# Digital_IO.net
KiCad netlist of a schematic drawn in Altium Designer
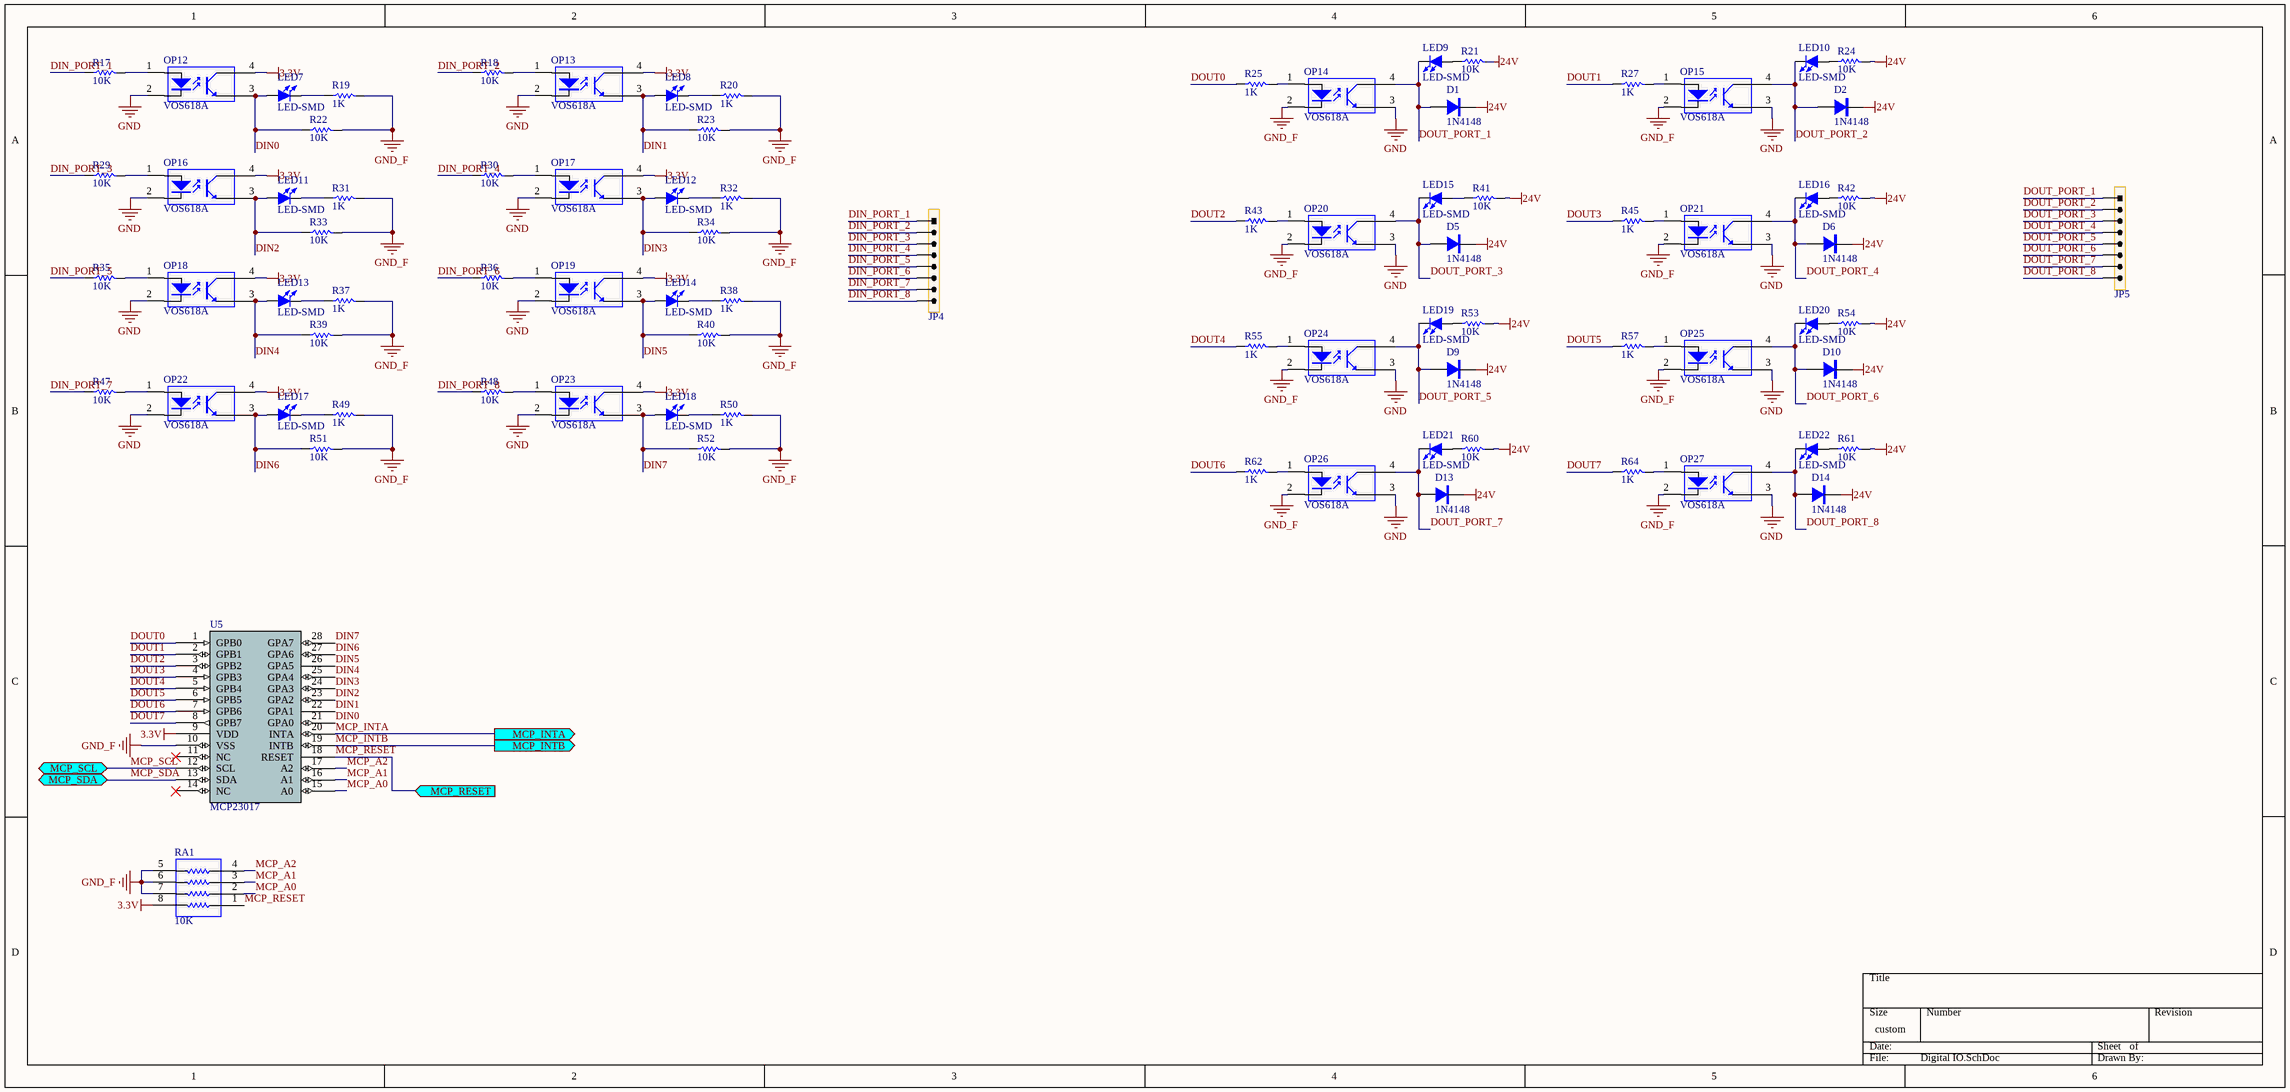
[diagram p0: Digital IO.SchDoc]

(export (version "E")
  (design (tool "Eeschema 10.0.6"))
  (components
    (comp (ref "D1")
      (value "1N4148")
      (footprint "SOD-323")
      (description "High speed switching diode")
      (fields (field (name "版权归属") "源创客"))
      (libsource (lib "Diode-Zener-Rectifier Bridge") (part "1N4148"))
    )
    (comp (ref "D2")
      (value "1N4148")
      (footprint "SOD-323")
      (description "High speed switching diode")
      (fields (field (name "版权归属") "源创客"))
      (libsource (lib "Diode-Zener-Rectifier Bridge") (part "1N4148"))
    )
    (comp (ref "D5")
      (value "1N4148")
      (footprint "SOD-323")
      (description "High speed switching diode")
      (fields (field (name "版权归属") "源创客"))
      (libsource (lib "Diode-Zener-Rectifier Bridge") (part "1N4148"))
    )
    (comp (ref "D6")
      (value "1N4148")
      (footprint "SOD-323")
      (description "High speed switching diode")
      (fields (field (name "版权归属") "源创客"))
      (libsource (lib "Diode-Zener-Rectifier Bridge") (part "1N4148"))
    )
    (comp (ref "D9")
      (value "1N4148")
      (footprint "SOD-323")
      (description "High speed switching diode")
      (fields (field (name "版权归属") "源创客"))
      (libsource (lib "Diode-Zener-Rectifier Bridge") (part "1N4148"))
    )
    (comp (ref "D10")
      (value "1N4148")
      (footprint "SOD-323")
      (description "High speed switching diode")
      (fields (field (name "版权归属") "源创客"))
      (libsource (lib "Diode-Zener-Rectifier Bridge") (part "1N4148"))
    )
    (comp (ref "D13")
      (value "1N4148")
      (footprint "SOD-323")
      (description "High speed switching diode")
      (fields (field (name "版权归属") "源创客"))
      (libsource (lib "Diode-Zener-Rectifier Bridge") (part "1N4148"))
    )
    (comp (ref "D14")
      (value "1N4148")
      (footprint "SOD-323")
      (description "High speed switching diode")
      (fields (field (name "版权归属") "源创客"))
      (libsource (lib "Diode-Zener-Rectifier Bridge") (part "1N4148"))
    )
    (comp (ref "JP4")
      (value "HDR-1X8")
      (footprint "KF-8P-BLK-H-3.81")
      (description "8P Connector")
      (fields (field (name "版权归属") "源创客"))
      (libsource (lib "Connectors") (part "Header 8"))
    )
    (comp (ref "JP5")
      (value "HDR-1X8")
      (footprint "KF-8P-BLK-H-3.81")
      (description "8P Connector")
      (fields (field (name "版权归属") "源创客"))
      (libsource (lib "Connectors") (part "Header 8"))
    )
    (comp (ref "LED7")
      (value "LED-SMD")
      (footprint "LED 0603G")
      (description "Patch LED")
      (fields (field (name "版权归属") "源创客"))
      (libsource (lib "LED") (part "LED-SMD"))
    )
    (comp (ref "LED8")
      (value "LED-SMD")
      (footprint "LED 0603G")
      (description "Patch LED")
      (fields (field (name "版权归属") "源创客"))
      (libsource (lib "LED") (part "LED-SMD"))
    )
    (comp (ref "LED9")
      (value "LED-SMD")
      (footprint "LED 0603B")
      (description "Patch LED")
      (fields (field (name "版权归属") "源创客"))
      (libsource (lib "LED") (part "LED-SMD"))
    )
    (comp (ref "LED10")
      (value "LED-SMD")
      (footprint "LED 0603B")
      (description "Patch LED")
      (fields (field (name "版权归属") "源创客"))
      (libsource (lib "LED") (part "LED-SMD"))
    )
    (comp (ref "LED11")
      (value "LED-SMD")
      (footprint "LED 0603G")
      (description "Patch LED")
      (fields (field (name "版权归属") "源创客"))
      (libsource (lib "LED") (part "LED-SMD"))
    )
    (comp (ref "LED12")
      (value "LED-SMD")
      (footprint "LED 0603G")
      (description "Patch LED")
      (fields (field (name "版权归属") "源创客"))
      (libsource (lib "LED") (part "LED-SMD"))
    )
    (comp (ref "LED13")
      (value "LED-SMD")
      (footprint "LED 0603G")
      (description "Patch LED")
      (fields (field (name "版权归属") "源创客"))
      (libsource (lib "LED") (part "LED-SMD"))
    )
    (comp (ref "LED14")
      (value "LED-SMD")
      (footprint "LED 0603G")
      (description "Patch LED")
      (fields (field (name "版权归属") "源创客"))
      (libsource (lib "LED") (part "LED-SMD"))
    )
    (comp (ref "LED15")
      (value "LED-SMD")
      (footprint "LED 0603B")
      (description "Patch LED")
      (fields (field (name "版权归属") "源创客"))
      (libsource (lib "LED") (part "LED-SMD"))
    )
    (comp (ref "LED16")
      (value "LED-SMD")
      (footprint "LED 0603B")
      (description "Patch LED")
      (fields (field (name "版权归属") "源创客"))
      (libsource (lib "LED") (part "LED-SMD"))
    )
    (comp (ref "LED17")
      (value "LED-SMD")
      (footprint "LED 0603G")
      (description "Patch LED")
      (fields (field (name "版权归属") "源创客"))
      (libsource (lib "LED") (part "LED-SMD"))
    )
    (comp (ref "LED18")
      (value "LED-SMD")
      (footprint "LED 0603G")
      (description "Patch LED")
      (fields (field (name "版权归属") "源创客"))
      (libsource (lib "LED") (part "LED-SMD"))
    )
    (comp (ref "LED19")
      (value "LED-SMD")
      (footprint "LED 0603B")
      (description "Patch LED")
      (fields (field (name "版权归属") "源创客"))
      (libsource (lib "LED") (part "LED-SMD"))
    )
    (comp (ref "LED20")
      (value "LED-SMD")
      (footprint "LED 0603B")
      (description "Patch LED")
      (fields (field (name "版权归属") "源创客"))
      (libsource (lib "LED") (part "LED-SMD"))
    )
    (comp (ref "LED21")
      (value "LED-SMD")
      (footprint "LED 0603B")
      (description "Patch LED")
      (fields (field (name "版权归属") "源创客"))
      (libsource (lib "LED") (part "LED-SMD"))
    )
    (comp (ref "LED22")
      (value "LED-SMD")
      (footprint "LED 0603B")
      (description "Patch LED")
      (fields (field (name "版权归属") "源创客"))
      (libsource (lib "LED") (part "LED-SMD"))
    )
    (comp (ref "OP12")
      (value "VOS618A")
      (footprint "VOS618A-SSOP4")
      (libsource (lib "Sensing Element") (part "VOS618A"))
    )
    (comp (ref "OP13")
      (value "VOS618A")
      (footprint "VOS618A-SSOP4")
      (libsource (lib "Sensing Element") (part "VOS618A"))
    )
    (comp (ref "OP14")
      (value "VOS618A")
      (footprint "VOS618A-SSOP4")
      (libsource (lib "Sensing Element") (part "VOS618A"))
    )
    (comp (ref "OP15")
      (value "VOS618A")
      (footprint "VOS618A-SSOP4")
      (libsource (lib "Sensing Element") (part "VOS618A"))
    )
    (comp (ref "OP16")
      (value "VOS618A")
      (footprint "VOS618A-SSOP4")
      (libsource (lib "Sensing Element") (part "VOS618A"))
    )
    (comp (ref "OP17")
      (value "VOS618A")
      (footprint "VOS618A-SSOP4")
      (libsource (lib "Sensing Element") (part "VOS618A"))
    )
    (comp (ref "OP18")
      (value "VOS618A")
      (footprint "VOS618A-SSOP4")
      (libsource (lib "Sensing Element") (part "VOS618A"))
    )
    (comp (ref "OP19")
      (value "VOS618A")
      (footprint "VOS618A-SSOP4")
      (libsource (lib "Sensing Element") (part "VOS618A"))
    )
    (comp (ref "OP20")
      (value "VOS618A")
      (footprint "VOS618A-SSOP4")
      (libsource (lib "Sensing Element") (part "VOS618A"))
    )
    (comp (ref "OP21")
      (value "VOS618A")
      (footprint "VOS618A-SSOP4")
      (libsource (lib "Sensing Element") (part "VOS618A"))
    )
    (comp (ref "OP22")
      (value "VOS618A")
      (footprint "VOS618A-SSOP4")
      (libsource (lib "Sensing Element") (part "VOS618A"))
    )
    (comp (ref "OP23")
      (value "VOS618A")
      (footprint "VOS618A-SSOP4")
      (libsource (lib "Sensing Element") (part "VOS618A"))
    )
    (comp (ref "OP24")
      (value "VOS618A")
      (footprint "VOS618A-SSOP4")
      (libsource (lib "Sensing Element") (part "VOS618A"))
    )
    (comp (ref "OP25")
      (value "VOS618A")
      (footprint "VOS618A-SSOP4")
      (libsource (lib "Sensing Element") (part "VOS618A"))
    )
    (comp (ref "OP26")
      (value "VOS618A")
      (footprint "VOS618A-SSOP4")
      (libsource (lib "Sensing Element") (part "VOS618A"))
    )
    (comp (ref "OP27")
      (value "VOS618A")
      (footprint "VOS618A-SSOP4")
      (libsource (lib "Sensing Element") (part "VOS618A"))
    )
    (comp (ref "R17")
      (value "10K")
      (footprint "R 0603")
      (description "Chip resistor")
      (fields (field (name "版权归属") "源创客"))
      (libsource (lib "Passive (Resistor-Capacitor-Inductor-Veristor-Ferrite)") (part "R"))
    )
    (comp (ref "R18")
      (value "10K")
      (footprint "R 0603")
      (description "Chip resistor")
      (fields (field (name "版权归属") "源创客"))
      (libsource (lib "Passive (Resistor-Capacitor-Inductor-Veristor-Ferrite)") (part "R"))
    )
    (comp (ref "R19")
      (value "1K")
      (footprint "R 0603")
      (description "Chip resistor")
      (fields (field (name "版权归属") "源创客"))
      (libsource (lib "Passive (Resistor-Capacitor-Inductor-Veristor-Ferrite)") (part "R"))
    )
    (comp (ref "R20")
      (value "1K")
      (footprint "R 0603")
      (description "Chip resistor")
      (fields (field (name "版权归属") "源创客"))
      (libsource (lib "Passive (Resistor-Capacitor-Inductor-Veristor-Ferrite)") (part "R"))
    )
    (comp (ref "R21")
      (value "10K")
      (footprint "R 0603")
      (description "Chip resistor")
      (fields (field (name "版权归属") "源创客"))
      (libsource (lib "Passive (Resistor-Capacitor-Inductor-Veristor-Ferrite)") (part "R"))
    )
    (comp (ref "R22")
      (value "10K")
      (footprint "R 0603")
      (description "Chip resistor")
      (fields (field (name "版权归属") "源创客"))
      (libsource (lib "Passive (Resistor-Capacitor-Inductor-Veristor-Ferrite)") (part "R"))
    )
    (comp (ref "R23")
      (value "10K")
      (footprint "R 0603")
      (description "Chip resistor")
      (fields (field (name "版权归属") "源创客"))
      (libsource (lib "Passive (Resistor-Capacitor-Inductor-Veristor-Ferrite)") (part "R"))
    )
    (comp (ref "R24")
      (value "10K")
      (footprint "R 0603")
      (description "Chip resistor")
      (fields (field (name "版权归属") "源创客"))
      (libsource (lib "Passive (Resistor-Capacitor-Inductor-Veristor-Ferrite)") (part "R"))
    )
    (comp (ref "R25")
      (value "1K")
      (footprint "R 0603")
      (description "Chip resistor")
      (fields (field (name "版权归属") "源创客"))
      (libsource (lib "Passive (Resistor-Capacitor-Inductor-Veristor-Ferrite)") (part "R"))
    )
    (comp (ref "R27")
      (value "1K")
      (footprint "R 0603")
      (description "Chip resistor")
      (fields (field (name "版权归属") "源创客"))
      (libsource (lib "Passive (Resistor-Capacitor-Inductor-Veristor-Ferrite)") (part "R"))
    )
    (comp (ref "R29")
      (value "10K")
      (footprint "R 0603")
      (description "Chip resistor")
      (fields (field (name "版权归属") "源创客"))
      (libsource (lib "Passive (Resistor-Capacitor-Inductor-Veristor-Ferrite)") (part "R"))
    )
    (comp (ref "R30")
      (value "10K")
      (footprint "R 0603")
      (description "Chip resistor")
      (fields (field (name "版权归属") "源创客"))
      (libsource (lib "Passive (Resistor-Capacitor-Inductor-Veristor-Ferrite)") (part "R"))
    )
    (comp (ref "R31")
      (value "1K")
      (footprint "R 0603")
      (description "Chip resistor")
      (fields (field (name "版权归属") "源创客"))
      (libsource (lib "Passive (Resistor-Capacitor-Inductor-Veristor-Ferrite)") (part "R"))
    )
    (comp (ref "R32")
      (value "1K")
      (footprint "R 0603")
      (description "Chip resistor")
      (fields (field (name "版权归属") "源创客"))
      (libsource (lib "Passive (Resistor-Capacitor-Inductor-Veristor-Ferrite)") (part "R"))
    )
    (comp (ref "R33")
      (value "10K")
      (footprint "R 0603")
      (description "Chip resistor")
      (fields (field (name "版权归属") "源创客"))
      (libsource (lib "Passive (Resistor-Capacitor-Inductor-Veristor-Ferrite)") (part "R"))
    )
    (comp (ref "R34")
      (value "10K")
      (footprint "R 0603")
      (description "Chip resistor")
      (fields (field (name "版权归属") "源创客"))
      (libsource (lib "Passive (Resistor-Capacitor-Inductor-Veristor-Ferrite)") (part "R"))
    )
    (comp (ref "R35")
      (value "10K")
      (footprint "R 0603")
      (description "Chip resistor")
      (fields (field (name "版权归属") "源创客"))
      (libsource (lib "Passive (Resistor-Capacitor-Inductor-Veristor-Ferrite)") (part "R"))
    )
    (comp (ref "R36")
      (value "10K")
      (footprint "R 0603")
      (description "Chip resistor")
      (fields (field (name "版权归属") "源创客"))
      (libsource (lib "Passive (Resistor-Capacitor-Inductor-Veristor-Ferrite)") (part "R"))
    )
    (comp (ref "R37")
      (value "1K")
      (footprint "R 0603")
      (description "Chip resistor")
      (fields (field (name "版权归属") "源创客"))
      (libsource (lib "Passive (Resistor-Capacitor-Inductor-Veristor-Ferrite)") (part "R"))
    )
    (comp (ref "R38")
      (value "1K")
      (footprint "R 0603")
      (description "Chip resistor")
      (fields (field (name "版权归属") "源创客"))
      (libsource (lib "Passive (Resistor-Capacitor-Inductor-Veristor-Ferrite)") (part "R"))
    )
    (comp (ref "R39")
      (value "10K")
      (footprint "R 0603")
      (description "Chip resistor")
      (fields (field (name "版权归属") "源创客"))
      (libsource (lib "Passive (Resistor-Capacitor-Inductor-Veristor-Ferrite)") (part "R"))
    )
    (comp (ref "R40")
      (value "10K")
      (footprint "R 0603")
      (description "Chip resistor")
      (fields (field (name "版权归属") "源创客"))
      (libsource (lib "Passive (Resistor-Capacitor-Inductor-Veristor-Ferrite)") (part "R"))
    )
    (comp (ref "R41")
      (value "10K")
      (footprint "R 0603")
      (description "Chip resistor")
      (fields (field (name "版权归属") "源创客"))
      (libsource (lib "Passive (Resistor-Capacitor-Inductor-Veristor-Ferrite)") (part "R"))
    )
    (comp (ref "R42")
      (value "10K")
      (footprint "R 0603")
      (description "Chip resistor")
      (fields (field (name "版权归属") "源创客"))
      (libsource (lib "Passive (Resistor-Capacitor-Inductor-Veristor-Ferrite)") (part "R"))
    )
    (comp (ref "R43")
      (value "1K")
      (footprint "R 0603")
      (description "Chip resistor")
      (fields (field (name "版权归属") "源创客"))
      (libsource (lib "Passive (Resistor-Capacitor-Inductor-Veristor-Ferrite)") (part "R"))
    )
    (comp (ref "R45")
      (value "1K")
      (footprint "R 0603")
      (description "Chip resistor")
      (fields (field (name "版权归属") "源创客"))
      (libsource (lib "Passive (Resistor-Capacitor-Inductor-Veristor-Ferrite)") (part "R"))
    )
    (comp (ref "R47")
      (value "10K")
      (footprint "R 0603")
      (description "Chip resistor")
      (fields (field (name "版权归属") "源创客"))
      (libsource (lib "Passive (Resistor-Capacitor-Inductor-Veristor-Ferrite)") (part "R"))
    )
    (comp (ref "R48")
      (value "10K")
      (footprint "R 0603")
      (description "Chip resistor")
      (fields (field (name "版权归属") "源创客"))
      (libsource (lib "Passive (Resistor-Capacitor-Inductor-Veristor-Ferrite)") (part "R"))
    )
    (comp (ref "R49")
      (value "1K")
      (footprint "R 0603")
      (description "Chip resistor")
      (fields (field (name "版权归属") "源创客"))
      (libsource (lib "Passive (Resistor-Capacitor-Inductor-Veristor-Ferrite)") (part "R"))
    )
    (comp (ref "R50")
      (value "1K")
      (footprint "R 0603")
      (description "Chip resistor")
      (fields (field (name "版权归属") "源创客"))
      (libsource (lib "Passive (Resistor-Capacitor-Inductor-Veristor-Ferrite)") (part "R"))
    )
    (comp (ref "R51")
      (value "10K")
      (footprint "R 0603")
      (description "Chip resistor")
      (fields (field (name "版权归属") "源创客"))
      (libsource (lib "Passive (Resistor-Capacitor-Inductor-Veristor-Ferrite)") (part "R"))
    )
    (comp (ref "R52")
      (value "10K")
      (footprint "R 0603")
      (description "Chip resistor")
      (fields (field (name "版权归属") "源创客"))
      (libsource (lib "Passive (Resistor-Capacitor-Inductor-Veristor-Ferrite)") (part "R"))
    )
    (comp (ref "R53")
      (value "10K")
      (footprint "R 0603")
      (description "Chip resistor")
      (fields (field (name "版权归属") "源创客"))
      (libsource (lib "Passive (Resistor-Capacitor-Inductor-Veristor-Ferrite)") (part "R"))
    )
    (comp (ref "R54")
      (value "10K")
      (footprint "R 0603")
      (description "Chip resistor")
      (fields (field (name "版权归属") "源创客"))
      (libsource (lib "Passive (Resistor-Capacitor-Inductor-Veristor-Ferrite)") (part "R"))
    )
    (comp (ref "R55")
      (value "1K")
      (footprint "R 0603")
      (description "Chip resistor")
      (fields (field (name "版权归属") "源创客"))
      (libsource (lib "Passive (Resistor-Capacitor-Inductor-Veristor-Ferrite)") (part "R"))
    )
    (comp (ref "R57")
      (value "1K")
      (footprint "R 0603")
      (description "Chip resistor")
      (fields (field (name "版权归属") "源创客"))
      (libsource (lib "Passive (Resistor-Capacitor-Inductor-Veristor-Ferrite)") (part "R"))
    )
    (comp (ref "R60")
      (value "10K")
      (footprint "R 0603")
      (description "Chip resistor")
      (fields (field (name "版权归属") "源创客"))
      (libsource (lib "Passive (Resistor-Capacitor-Inductor-Veristor-Ferrite)") (part "R"))
    )
    (comp (ref "R61")
      (value "10K")
      (footprint "R 0603")
      (description "Chip resistor")
      (fields (field (name "版权归属") "源创客"))
      (libsource (lib "Passive (Resistor-Capacitor-Inductor-Veristor-Ferrite)") (part "R"))
    )
    (comp (ref "R62")
      (value "1K")
      (footprint "R 0603")
      (description "Chip resistor")
      (fields (field (name "版权归属") "源创客"))
      (libsource (lib "Passive (Resistor-Capacitor-Inductor-Veristor-Ferrite)") (part "R"))
    )
    (comp (ref "R64")
      (value "1K")
      (footprint "R 0603")
      (description "Chip resistor")
      (fields (field (name "版权归属") "源创客"))
      (libsource (lib "Passive (Resistor-Capacitor-Inductor-Veristor-Ferrite)") (part "R"))
    )
    (comp (ref "RA1")
      (value "10K")
      (footprint "RA1206 (4x0603)")
      (description "4 way Chip Resistor Array")
      (libsource (lib "Passive (Resistor-Capacitor-Inductor-Veristor-Ferrite)") (part "R-ARR"))
    )
    (comp (ref "U5")
      (value "MCP23017")
      (footprint "SOIC28")
      (libsource (lib "Integrated Circuit") (part "MCP23017"))
    )
  )
  (nets
    (net (code "1") (name "/DIN0") (class "Default")
      (node (ref "LED7") (pin "1") (pinfunction "A_1") (pintype "passive"))
      (node (ref "OP12") (pin "3") (pinfunction "E_3") (pintype "passive"))
      (node (ref "R22") (pin "1") (pinfunction "1_1") (pintype "passive"))
      (node (ref "U5") (pin "21") (pinfunction "GPA0_21") (pintype "bidirectional"))
    )
    (net (code "2") (name "/DIN1") (class "Default")
      (node (ref "LED8") (pin "1") (pinfunction "A_1") (pintype "passive"))
      (node (ref "OP13") (pin "3") (pinfunction "E_3") (pintype "passive"))
      (node (ref "R23") (pin "1") (pinfunction "1_1") (pintype "passive"))
      (node (ref "U5") (pin "22") (pinfunction "GPA1_22") (pintype "power_in"))
    )
    (net (code "3") (name "/DIN2") (class "Default")
      (node (ref "LED11") (pin "1") (pinfunction "A_1") (pintype "passive"))
      (node (ref "OP16") (pin "3") (pinfunction "E_3") (pintype "passive"))
      (node (ref "R33") (pin "1") (pinfunction "1_1") (pintype "passive"))
      (node (ref "U5") (pin "23") (pinfunction "GPA2_23") (pintype "bidirectional"))
    )
    (net (code "4") (name "/DIN3") (class "Default")
      (node (ref "LED12") (pin "1") (pinfunction "A_1") (pintype "passive"))
      (node (ref "OP17") (pin "3") (pinfunction "E_3") (pintype "passive"))
      (node (ref "R34") (pin "1") (pinfunction "1_1") (pintype "passive"))
      (node (ref "U5") (pin "24") (pinfunction "GPA3_24") (pintype "bidirectional"))
    )
    (net (code "5") (name "/DIN4") (class "Default")
      (node (ref "LED13") (pin "1") (pinfunction "A_1") (pintype "passive"))
      (node (ref "OP18") (pin "3") (pinfunction "E_3") (pintype "passive"))
      (node (ref "R39") (pin "1") (pinfunction "1_1") (pintype "passive"))
      (node (ref "U5") (pin "25") (pinfunction "GPA4_25") (pintype "bidirectional"))
    )
    (net (code "6") (name "/DIN5") (class "Default")
      (node (ref "LED14") (pin "1") (pinfunction "A_1") (pintype "passive"))
      (node (ref "OP19") (pin "3") (pinfunction "E_3") (pintype "passive"))
      (node (ref "R40") (pin "1") (pinfunction "1_1") (pintype "passive"))
      (node (ref "U5") (pin "26") (pinfunction "GPA5_26") (pintype "power_in"))
    )
    (net (code "7") (name "/DIN6") (class "Default")
      (node (ref "LED17") (pin "1") (pinfunction "A_1") (pintype "passive"))
      (node (ref "OP22") (pin "3") (pinfunction "E_3") (pintype "passive"))
      (node (ref "R51") (pin "1") (pinfunction "1_1") (pintype "passive"))
      (node (ref "U5") (pin "27") (pinfunction "GPA6_27") (pintype "bidirectional"))
    )
    (net (code "8") (name "/DIN7") (class "Default")
      (node (ref "LED18") (pin "1") (pinfunction "A_1") (pintype "passive"))
      (node (ref "OP23") (pin "3") (pinfunction "E_3") (pintype "passive"))
      (node (ref "R52") (pin "1") (pinfunction "1_1") (pintype "passive"))
      (node (ref "U5") (pin "28") (pinfunction "GPA7_28") (pintype "bidirectional"))
    )
    (net (code "9") (name "/DIN_PORT_1") (class "Default")
      (node (ref "JP4") (pin "1") (pintype "passive"))
      (node (ref "R17") (pin "1") (pinfunction "1_1") (pintype "passive"))
    )
    (net (code "10") (name "/DIN_PORT_2") (class "Default")
      (node (ref "JP4") (pin "2") (pintype "passive"))
      (node (ref "R18") (pin "1") (pinfunction "1_1") (pintype "passive"))
    )
    (net (code "11") (name "/DIN_PORT_3") (class "Default")
      (node (ref "JP4") (pin "3") (pintype "passive"))
      (node (ref "R29") (pin "1") (pinfunction "1_1") (pintype "passive"))
    )
    (net (code "12") (name "/DIN_PORT_4") (class "Default")
      (node (ref "JP4") (pin "4") (pintype "passive"))
      (node (ref "R30") (pin "1") (pinfunction "1_1") (pintype "passive"))
    )
    (net (code "13") (name "/DIN_PORT_5") (class "Default")
      (node (ref "JP4") (pin "5") (pintype "passive"))
      (node (ref "R35") (pin "1") (pinfunction "1_1") (pintype "passive"))
    )
    (net (code "14") (name "/DIN_PORT_6") (class "Default")
      (node (ref "JP4") (pin "6") (pintype "passive"))
      (node (ref "R36") (pin "1") (pinfunction "1_1") (pintype "passive"))
    )
    (net (code "15") (name "/DIN_PORT_7") (class "Default")
      (node (ref "JP4") (pin "7") (pintype "passive"))
      (node (ref "R47") (pin "1") (pinfunction "1_1") (pintype "passive"))
    )
    (net (code "16") (name "/DIN_PORT_8") (class "Default")
      (node (ref "JP4") (pin "8") (pintype "passive"))
      (node (ref "R48") (pin "1") (pinfunction "1_1") (pintype "passive"))
    )
    (net (code "17") (name "/DOUT0") (class "Default")
      (node (ref "R25") (pin "1") (pinfunction "1_1") (pintype "passive"))
      (node (ref "U5") (pin "1") (pinfunction "GPB0_1") (pintype "input"))
    )
    (net (code "18") (name "/DOUT1") (class "Default")
      (node (ref "R27") (pin "1") (pinfunction "1_1") (pintype "passive"))
      (node (ref "U5") (pin "2") (pinfunction "GPB1_2") (pintype "bidirectional"))
    )
    (net (code "19") (name "/DOUT2") (class "Default")
      (node (ref "R43") (pin "1") (pinfunction "1_1") (pintype "passive"))
      (node (ref "U5") (pin "3") (pinfunction "GPB2_3") (pintype "bidirectional"))
    )
    (net (code "20") (name "/DOUT3") (class "Default")
      (node (ref "R45") (pin "1") (pinfunction "1_1") (pintype "passive"))
      (node (ref "U5") (pin "4") (pinfunction "GPB3_4") (pintype "input"))
    )
    (net (code "21") (name "/DOUT4") (class "Default")
      (node (ref "R55") (pin "1") (pinfunction "1_1") (pintype "passive"))
      (node (ref "U5") (pin "5") (pinfunction "GPB4_5") (pintype "input"))
    )
    (net (code "22") (name "/DOUT5") (class "Default")
      (node (ref "R57") (pin "1") (pinfunction "1_1") (pintype "passive"))
      (node (ref "U5") (pin "6") (pinfunction "GPB5_6") (pintype "input"))
    )
    (net (code "23") (name "/DOUT6") (class "Default")
      (node (ref "R62") (pin "1") (pinfunction "1_1") (pintype "passive"))
      (node (ref "U5") (pin "7") (pinfunction "GPB6_7") (pintype "input"))
    )
    (net (code "24") (name "/DOUT7") (class "Default")
      (node (ref "R64") (pin "1") (pinfunction "1_1") (pintype "passive"))
      (node (ref "U5") (pin "8") (pinfunction "GPB7_8") (pintype "output"))
    )
    (net (code "25") (name "/DOUT_PORT_1") (class "Default")
      (node (ref "D1") (pin "1") (pinfunction "A_1") (pintype "passive"))
      (node (ref "JP5") (pin "1") (pintype "passive"))
      (node (ref "LED9") (pin "2") (pinfunction "K_2") (pintype "passive"))
      (node (ref "OP14") (pin "4") (pinfunction "C_4") (pintype "passive"))
    )
    (net (code "26") (name "/DOUT_PORT_2") (class "Default")
      (node (ref "D2") (pin "1") (pinfunction "A_1") (pintype "passive"))
      (node (ref "JP5") (pin "2") (pintype "passive"))
      (node (ref "LED10") (pin "2") (pinfunction "K_2") (pintype "passive"))
      (node (ref "OP15") (pin "4") (pinfunction "C_4") (pintype "passive"))
    )
    (net (code "27") (name "/DOUT_PORT_3") (class "Default")
      (node (ref "D5") (pin "1") (pinfunction "A_1") (pintype "passive"))
      (node (ref "JP5") (pin "3") (pintype "passive"))
      (node (ref "LED15") (pin "2") (pinfunction "K_2") (pintype "passive"))
      (node (ref "OP20") (pin "4") (pinfunction "C_4") (pintype "passive"))
    )
    (net (code "28") (name "/DOUT_PORT_4") (class "Default")
      (node (ref "D6") (pin "1") (pinfunction "A_1") (pintype "passive"))
      (node (ref "JP5") (pin "4") (pintype "passive"))
      (node (ref "LED16") (pin "2") (pinfunction "K_2") (pintype "passive"))
      (node (ref "OP21") (pin "4") (pinfunction "C_4") (pintype "passive"))
    )
    (net (code "29") (name "/DOUT_PORT_5") (class "Default")
      (node (ref "D9") (pin "1") (pinfunction "A_1") (pintype "passive"))
      (node (ref "JP5") (pin "5") (pintype "passive"))
      (node (ref "LED19") (pin "2") (pinfunction "K_2") (pintype "passive"))
      (node (ref "OP24") (pin "4") (pinfunction "C_4") (pintype "passive"))
    )
    (net (code "30") (name "/DOUT_PORT_6") (class "Default")
      (node (ref "D10") (pin "1") (pinfunction "A_1") (pintype "passive"))
      (node (ref "JP5") (pin "6") (pintype "passive"))
      (node (ref "LED20") (pin "2") (pinfunction "K_2") (pintype "passive"))
      (node (ref "OP25") (pin "4") (pinfunction "C_4") (pintype "passive"))
    )
    (net (code "31") (name "/DOUT_PORT_7") (class "Default")
      (node (ref "D13") (pin "1") (pinfunction "A_1") (pintype "passive"))
      (node (ref "JP5") (pin "7") (pintype "passive"))
      (node (ref "LED21") (pin "2") (pinfunction "K_2") (pintype "passive"))
      (node (ref "OP26") (pin "4") (pinfunction "C_4") (pintype "passive"))
    )
    (net (code "32") (name "/DOUT_PORT_8") (class "Default")
      (node (ref "D14") (pin "1") (pinfunction "A_1") (pintype "passive"))
      (node (ref "JP5") (pin "8") (pintype "passive"))
      (node (ref "LED22") (pin "2") (pinfunction "K_2") (pintype "passive"))
      (node (ref "OP27") (pin "4") (pinfunction "C_4") (pintype "passive"))
    )
    (net (code "33") (name "/MCP_A0") (class "Default")
      (node (ref "RA1") (pin "2") (pinfunction "2_2") (pintype "passive"))
      (node (ref "U5") (pin "15") (pinfunction "A0_15") (pintype "bidirectional"))
    )
    (net (code "34") (name "/MCP_A1") (class "Default")
      (node (ref "RA1") (pin "3") (pinfunction "3_3") (pintype "passive"))
      (node (ref "U5") (pin "16") (pinfunction "A1_16") (pintype "bidirectional"))
    )
    (net (code "35") (name "/MCP_A2") (class "Default")
      (node (ref "RA1") (pin "4") (pinfunction "4_4") (pintype "passive"))
      (node (ref "U5") (pin "17") (pinfunction "A2_17") (pintype "bidirectional"))
    )
    (net (code "36") (name "/MCP_INTA") (class "Default")
      (node (ref "U5") (pin "20") (pinfunction "INTA_20") (pintype "bidirectional"))
    )
    (net (code "37") (name "/MCP_INTB") (class "Default")
      (node (ref "U5") (pin "19") (pinfunction "INTB_19") (pintype "bidirectional"))
    )
    (net (code "38") (name "/MCP_RESET") (class "Default")
      (node (ref "RA1") (pin "1") (pinfunction "1_1") (pintype "passive"))
      (node (ref "U5") (pin "18") (pinfunction "RESET_18") (pintype "power_in"))
    )
    (net (code "39") (name "/MCP_SCL") (class "Default")
      (node (ref "U5") (pin "12") (pinfunction "SCL_12") (pintype "bidirectional"))
    )
    (net (code "40") (name "/MCP_SDA") (class "Default")
      (node (ref "U5") (pin "13") (pinfunction "SDA_13") (pintype "bidirectional"))
    )
    (net (code "41") (name "3.3V") (class "Default")
      (node (ref "OP12") (pin "4") (pinfunction "C_4") (pintype "passive"))
      (node (ref "OP13") (pin "4") (pinfunction "C_4") (pintype "passive"))
      (node (ref "OP16") (pin "4") (pinfunction "C_4") (pintype "passive"))
      (node (ref "OP17") (pin "4") (pinfunction "C_4") (pintype "passive"))
      (node (ref "OP18") (pin "4") (pinfunction "C_4") (pintype "passive"))
      (node (ref "OP19") (pin "4") (pinfunction "C_4") (pintype "passive"))
      (node (ref "OP22") (pin "4") (pinfunction "C_4") (pintype "passive"))
      (node (ref "OP23") (pin "4") (pinfunction "C_4") (pintype "passive"))
      (node (ref "RA1") (pin "8") (pinfunction "8_8") (pintype "passive"))
      (node (ref "U5") (pin "9") (pinfunction "VDD_9") (pintype "power_in"))
    )
    (net (code "42") (name "24V") (class "Default")
      (node (ref "D1") (pin "2") (pinfunction "K_2") (pintype "passive"))
      (node (ref "D10") (pin "2") (pinfunction "K_2") (pintype "passive"))
      (node (ref "D13") (pin "2") (pinfunction "K_2") (pintype "passive"))
      (node (ref "D14") (pin "2") (pinfunction "K_2") (pintype "passive"))
      (node (ref "D2") (pin "2") (pinfunction "K_2") (pintype "passive"))
      (node (ref "D5") (pin "2") (pinfunction "K_2") (pintype "passive"))
      (node (ref "D6") (pin "2") (pinfunction "K_2") (pintype "passive"))
      (node (ref "D9") (pin "2") (pinfunction "K_2") (pintype "passive"))
      (node (ref "R21") (pin "2") (pinfunction "2_2") (pintype "passive"))
      (node (ref "R24") (pin "2") (pinfunction "2_2") (pintype "passive"))
      (node (ref "R41") (pin "2") (pinfunction "2_2") (pintype "passive"))
      (node (ref "R42") (pin "2") (pinfunction "2_2") (pintype "passive"))
      (node (ref "R53") (pin "2") (pinfunction "2_2") (pintype "passive"))
      (node (ref "R54") (pin "2") (pinfunction "2_2") (pintype "passive"))
      (node (ref "R60") (pin "2") (pinfunction "2_2") (pintype "passive"))
      (node (ref "R61") (pin "2") (pinfunction "2_2") (pintype "passive"))
    )
    (net (code "43") (name "GND") (class "Default")
      (node (ref "OP12") (pin "2") (pinfunction "K_2") (pintype "passive"))
      (node (ref "OP13") (pin "2") (pinfunction "K_2") (pintype "passive"))
      (node (ref "OP14") (pin "3") (pinfunction "E_3") (pintype "passive"))
      (node (ref "OP15") (pin "3") (pinfunction "E_3") (pintype "passive"))
      (node (ref "OP16") (pin "2") (pinfunction "K_2") (pintype "passive"))
      (node (ref "OP17") (pin "2") (pinfunction "K_2") (pintype "passive"))
      (node (ref "OP18") (pin "2") (pinfunction "K_2") (pintype "passive"))
      (node (ref "OP19") (pin "2") (pinfunction "K_2") (pintype "passive"))
      (node (ref "OP20") (pin "3") (pinfunction "E_3") (pintype "passive"))
      (node (ref "OP21") (pin "3") (pinfunction "E_3") (pintype "passive"))
      (node (ref "OP22") (pin "2") (pinfunction "K_2") (pintype "passive"))
      (node (ref "OP23") (pin "2") (pinfunction "K_2") (pintype "passive"))
      (node (ref "OP24") (pin "3") (pinfunction "E_3") (pintype "passive"))
      (node (ref "OP25") (pin "3") (pinfunction "E_3") (pintype "passive"))
      (node (ref "OP26") (pin "3") (pinfunction "E_3") (pintype "passive"))
      (node (ref "OP27") (pin "3") (pinfunction "E_3") (pintype "passive"))
    )
    (net (code "44") (name "GND_F") (class "Default")
      (node (ref "OP14") (pin "2") (pinfunction "K_2") (pintype "passive"))
      (node (ref "OP15") (pin "2") (pinfunction "K_2") (pintype "passive"))
      (node (ref "OP20") (pin "2") (pinfunction "K_2") (pintype "passive"))
      (node (ref "OP21") (pin "2") (pinfunction "K_2") (pintype "passive"))
      (node (ref "OP24") (pin "2") (pinfunction "K_2") (pintype "passive"))
      (node (ref "OP25") (pin "2") (pinfunction "K_2") (pintype "passive"))
      (node (ref "OP26") (pin "2") (pinfunction "K_2") (pintype "passive"))
      (node (ref "OP27") (pin "2") (pinfunction "K_2") (pintype "passive"))
      (node (ref "R19") (pin "2") (pinfunction "2_2") (pintype "passive"))
      (node (ref "R20") (pin "2") (pinfunction "2_2") (pintype "passive"))
      (node (ref "R22") (pin "2") (pinfunction "2_2") (pintype "passive"))
      (node (ref "R23") (pin "2") (pinfunction "2_2") (pintype "passive"))
      (node (ref "R31") (pin "2") (pinfunction "2_2") (pintype "passive"))
      (node (ref "R32") (pin "2") (pinfunction "2_2") (pintype "passive"))
      (node (ref "R33") (pin "2") (pinfunction "2_2") (pintype "passive"))
      (node (ref "R34") (pin "2") (pinfunction "2_2") (pintype "passive"))
      (node (ref "R37") (pin "2") (pinfunction "2_2") (pintype "passive"))
      (node (ref "R38") (pin "2") (pinfunction "2_2") (pintype "passive"))
      (node (ref "R39") (pin "2") (pinfunction "2_2") (pintype "passive"))
      (node (ref "R40") (pin "2") (pinfunction "2_2") (pintype "passive"))
      (node (ref "R49") (pin "2") (pinfunction "2_2") (pintype "passive"))
      (node (ref "R50") (pin "2") (pinfunction "2_2") (pintype "passive"))
      (node (ref "R51") (pin "2") (pinfunction "2_2") (pintype "passive"))
      (node (ref "R52") (pin "2") (pinfunction "2_2") (pintype "passive"))
      (node (ref "RA1") (pin "5") (pinfunction "5_5") (pintype "passive"))
      (node (ref "RA1") (pin "6") (pinfunction "6_6") (pintype "passive"))
      (node (ref "RA1") (pin "7") (pinfunction "7_7") (pintype "passive"))
      (node (ref "U5") (pin "10") (pinfunction "VSS_10") (pintype "bidirectional"))
    )
    (net (code "45") (name "Net-(LED7-K)") (class "Default")
      (node (ref "LED7") (pin "2") (pinfunction "K_2") (pintype "passive"))
      (node (ref "R19") (pin "1") (pinfunction "1_1") (pintype "passive"))
    )
    (net (code "46") (name "Net-(LED8-K)") (class "Default")
      (node (ref "LED8") (pin "2") (pinfunction "K_2") (pintype "passive"))
      (node (ref "R20") (pin "1") (pinfunction "1_1") (pintype "passive"))
    )
    (net (code "47") (name "Net-(LED9-A)") (class "Default")
      (node (ref "LED9") (pin "1") (pinfunction "A_1") (pintype "passive"))
      (node (ref "R21") (pin "1") (pinfunction "1_1") (pintype "passive"))
    )
    (net (code "48") (name "Net-(LED10-A)") (class "Default")
      (node (ref "LED10") (pin "1") (pinfunction "A_1") (pintype "passive"))
      (node (ref "R24") (pin "1") (pinfunction "1_1") (pintype "passive"))
    )
    (net (code "49") (name "Net-(LED11-K)") (class "Default")
      (node (ref "LED11") (pin "2") (pinfunction "K_2") (pintype "passive"))
      (node (ref "R31") (pin "1") (pinfunction "1_1") (pintype "passive"))
    )
    (net (code "50") (name "Net-(LED12-K)") (class "Default")
      (node (ref "LED12") (pin "2") (pinfunction "K_2") (pintype "passive"))
      (node (ref "R32") (pin "1") (pinfunction "1_1") (pintype "passive"))
    )
    (net (code "51") (name "Net-(LED13-K)") (class "Default")
      (node (ref "LED13") (pin "2") (pinfunction "K_2") (pintype "passive"))
      (node (ref "R37") (pin "1") (pinfunction "1_1") (pintype "passive"))
    )
    (net (code "52") (name "Net-(LED14-K)") (class "Default")
      (node (ref "LED14") (pin "2") (pinfunction "K_2") (pintype "passive"))
      (node (ref "R38") (pin "1") (pinfunction "1_1") (pintype "passive"))
    )
    (net (code "53") (name "Net-(LED15-A)") (class "Default")
      (node (ref "LED15") (pin "1") (pinfunction "A_1") (pintype "passive"))
      (node (ref "R41") (pin "1") (pinfunction "1_1") (pintype "passive"))
    )
    (net (code "54") (name "Net-(LED16-A)") (class "Default")
      (node (ref "LED16") (pin "1") (pinfunction "A_1") (pintype "passive"))
      (node (ref "R42") (pin "1") (pinfunction "1_1") (pintype "passive"))
    )
    (net (code "55") (name "Net-(LED17-K)") (class "Default")
      (node (ref "LED17") (pin "2") (pinfunction "K_2") (pintype "passive"))
      (node (ref "R49") (pin "1") (pinfunction "1_1") (pintype "passive"))
    )
    (net (code "56") (name "Net-(LED18-K)") (class "Default")
      (node (ref "LED18") (pin "2") (pinfunction "K_2") (pintype "passive"))
      (node (ref "R50") (pin "1") (pinfunction "1_1") (pintype "passive"))
    )
    (net (code "57") (name "Net-(LED19-A)") (class "Default")
      (node (ref "LED19") (pin "1") (pinfunction "A_1") (pintype "passive"))
      (node (ref "R53") (pin "1") (pinfunction "1_1") (pintype "passive"))
    )
    (net (code "58") (name "Net-(LED20-A)") (class "Default")
      (node (ref "LED20") (pin "1") (pinfunction "A_1") (pintype "passive"))
      (node (ref "R54") (pin "1") (pinfunction "1_1") (pintype "passive"))
    )
    (net (code "59") (name "Net-(LED21-A)") (class "Default")
      (node (ref "LED21") (pin "1") (pinfunction "A_1") (pintype "passive"))
      (node (ref "R60") (pin "1") (pinfunction "1_1") (pintype "passive"))
    )
    (net (code "60") (name "Net-(LED22-A)") (class "Default")
      (node (ref "LED22") (pin "1") (pinfunction "A_1") (pintype "passive"))
      (node (ref "R61") (pin "1") (pinfunction "1_1") (pintype "passive"))
    )
    (net (code "61") (name "Net-(OP12-A)") (class "Default")
      (node (ref "OP12") (pin "1") (pinfunction "A_1") (pintype "passive"))
      (node (ref "R17") (pin "2") (pinfunction "2_2") (pintype "passive"))
    )
    (net (code "62") (name "Net-(OP13-A)") (class "Default")
      (node (ref "OP13") (pin "1") (pinfunction "A_1") (pintype "passive"))
      (node (ref "R18") (pin "2") (pinfunction "2_2") (pintype "passive"))
    )
    (net (code "63") (name "Net-(OP14-A)") (class "Default")
      (node (ref "OP14") (pin "1") (pinfunction "A_1") (pintype "passive"))
      (node (ref "R25") (pin "2") (pinfunction "2_2") (pintype "passive"))
    )
    (net (code "64") (name "Net-(OP15-A)") (class "Default")
      (node (ref "OP15") (pin "1") (pinfunction "A_1") (pintype "passive"))
      (node (ref "R27") (pin "2") (pinfunction "2_2") (pintype "passive"))
    )
    (net (code "65") (name "Net-(OP16-A)") (class "Default")
      (node (ref "OP16") (pin "1") (pinfunction "A_1") (pintype "passive"))
      (node (ref "R29") (pin "2") (pinfunction "2_2") (pintype "passive"))
    )
    (net (code "66") (name "Net-(OP17-A)") (class "Default")
      (node (ref "OP17") (pin "1") (pinfunction "A_1") (pintype "passive"))
      (node (ref "R30") (pin "2") (pinfunction "2_2") (pintype "passive"))
    )
    (net (code "67") (name "Net-(OP18-A)") (class "Default")
      (node (ref "OP18") (pin "1") (pinfunction "A_1") (pintype "passive"))
      (node (ref "R35") (pin "2") (pinfunction "2_2") (pintype "passive"))
    )
    (net (code "68") (name "Net-(OP19-A)") (class "Default")
      (node (ref "OP19") (pin "1") (pinfunction "A_1") (pintype "passive"))
      (node (ref "R36") (pin "2") (pinfunction "2_2") (pintype "passive"))
    )
    (net (code "69") (name "Net-(OP20-A)") (class "Default")
      (node (ref "OP20") (pin "1") (pinfunction "A_1") (pintype "passive"))
      (node (ref "R43") (pin "2") (pinfunction "2_2") (pintype "passive"))
    )
    (net (code "70") (name "Net-(OP21-A)") (class "Default")
      (node (ref "OP21") (pin "1") (pinfunction "A_1") (pintype "passive"))
      (node (ref "R45") (pin "2") (pinfunction "2_2") (pintype "passive"))
    )
    (net (code "71") (name "Net-(OP22-A)") (class "Default")
      (node (ref "OP22") (pin "1") (pinfunction "A_1") (pintype "passive"))
      (node (ref "R47") (pin "2") (pinfunction "2_2") (pintype "passive"))
    )
    (net (code "72") (name "Net-(OP23-A)") (class "Default")
      (node (ref "OP23") (pin "1") (pinfunction "A_1") (pintype "passive"))
      (node (ref "R48") (pin "2") (pinfunction "2_2") (pintype "passive"))
    )
    (net (code "73") (name "Net-(OP24-A)") (class "Default")
      (node (ref "OP24") (pin "1") (pinfunction "A_1") (pintype "passive"))
      (node (ref "R55") (pin "2") (pinfunction "2_2") (pintype "passive"))
    )
    (net (code "74") (name "Net-(OP25-A)") (class "Default")
      (node (ref "OP25") (pin "1") (pinfunction "A_1") (pintype "passive"))
      (node (ref "R57") (pin "2") (pinfunction "2_2") (pintype "passive"))
    )
    (net (code "75") (name "Net-(OP26-A)") (class "Default")
      (node (ref "OP26") (pin "1") (pinfunction "A_1") (pintype "passive"))
      (node (ref "R62") (pin "2") (pinfunction "2_2") (pintype "passive"))
    )
    (net (code "76") (name "Net-(OP27-A)") (class "Default")
      (node (ref "OP27") (pin "1") (pinfunction "A_1") (pintype "passive"))
      (node (ref "R64") (pin "2") (pinfunction "2_2") (pintype "passive"))
    )
    (net (code "77") (name "unconnected-(U5-NC-Pad11)") (class "Default")
      (node (ref "U5") (pin "11") (pinfunction "NC_11") (pintype "bidirectional+no_connect"))
    )
    (net (code "78") (name "unconnected-(U5-NC-Pad14)") (class "Default")
      (node (ref "U5") (pin "14") (pinfunction "NC_14") (pintype "bidirectional+no_connect"))
    )
  )
)
